# LED-Controller.net
KiCad netlist of a schematic drawn in EAGLE
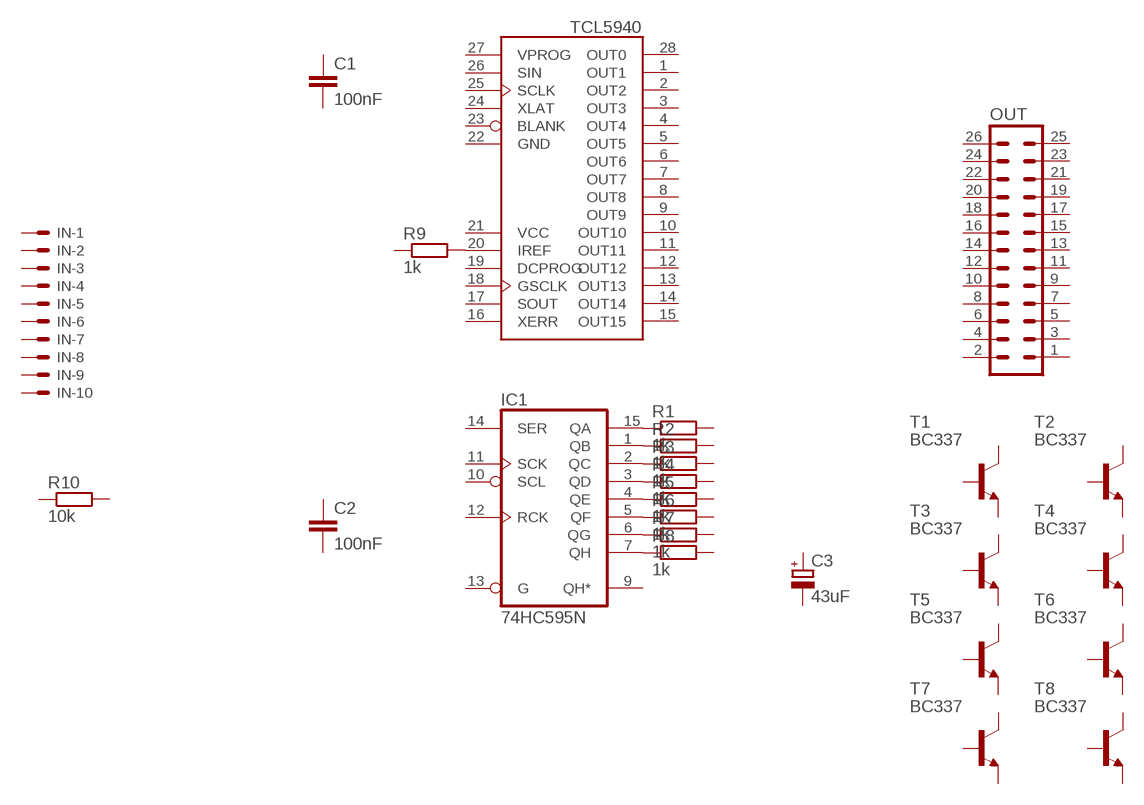
[diagram p0: schematic, sheet 1]

(export (version "E")
  (design (tool "Eeschema 10.0.6"))
  (components
    (comp (ref "C1")
      (value "100nF")
      (footprint "eagle-import:C025-024X044")
      (libsource (lib "eagle-import") (part "C-EU025-024X044"))
    )
    (comp (ref "C2")
      (value "100nF")
      (footprint "eagle-import:C025-024X044")
      (libsource (lib "eagle-import") (part "C-EU025-024X044"))
    )
    (comp (ref "C3")
      (value "43uF")
      (footprint "eagle-import:E2,5-6E")
      (libsource (lib "eagle-import") (part "CPOL-EUE2,5-6E"))
    )
    (comp (ref "IC1")
      (value "74HC595N")
      (footprint "eagle-import:DIL16")
      (libsource (lib "eagle-import") (part "74595NHC"))
    )
    (comp (ref "IC2")
      (value "TCL5940")
      (footprint "eagle-import:DIP28")
      (libsource (lib "eagle-import") (part "TCL5940"))
    )
    (comp (ref "IN")
      (value "KK-156-10")
      (footprint "eagle-import:KK-156-10")
      (libsource (lib "eagle-import") (part "KK-156-10"))
    )
    (comp (ref "OUT")
      (value "ML26")
      (footprint "eagle-import:ML26")
      (libsource (lib "eagle-import") (part "ML26"))
    )
    (comp (ref "R1")
      (value "1k")
      (footprint "eagle-import:0204_7")
      (libsource (lib "eagle-import") (part "R-EU_0204/7"))
    )
    (comp (ref "R2")
      (value "1k")
      (footprint "eagle-import:0204_7")
      (libsource (lib "eagle-import") (part "R-EU_0204/7"))
    )
    (comp (ref "R3")
      (value "1k")
      (footprint "eagle-import:0204_7")
      (libsource (lib "eagle-import") (part "R-EU_0204/7"))
    )
    (comp (ref "R4")
      (value "1k")
      (footprint "eagle-import:0204_7")
      (libsource (lib "eagle-import") (part "R-EU_0204/7"))
    )
    (comp (ref "R5")
      (value "1k")
      (footprint "eagle-import:0204_7")
      (libsource (lib "eagle-import") (part "R-EU_0204/7"))
    )
    (comp (ref "R6")
      (value "1k")
      (footprint "eagle-import:0204_7")
      (libsource (lib "eagle-import") (part "R-EU_0204/7"))
    )
    (comp (ref "R7")
      (value "1k")
      (footprint "eagle-import:0204_7")
      (libsource (lib "eagle-import") (part "R-EU_0204/7"))
    )
    (comp (ref "R8")
      (value "1k")
      (footprint "eagle-import:0204_7")
      (libsource (lib "eagle-import") (part "R-EU_0204/7"))
    )
    (comp (ref "R9")
      (value "1k")
      (footprint "eagle-import:0204_7")
      (libsource (lib "eagle-import") (part "R-EU_0204/7"))
    )
    (comp (ref "R10")
      (value "10k")
      (footprint "eagle-import:0204_7")
      (libsource (lib "eagle-import") (part "R-EU_0204/7"))
    )
    (comp (ref "T1")
      (value "BC337")
      (footprint "eagle-import:TO92")
      (libsource (lib "eagle-import") (part "BC337"))
    )
    (comp (ref "T2")
      (value "BC337")
      (footprint "eagle-import:TO92")
      (libsource (lib "eagle-import") (part "BC337"))
    )
    (comp (ref "T3")
      (value "BC337")
      (footprint "eagle-import:TO92")
      (libsource (lib "eagle-import") (part "BC337"))
    )
    (comp (ref "T4")
      (value "BC337")
      (footprint "eagle-import:TO92")
      (libsource (lib "eagle-import") (part "BC337"))
    )
    (comp (ref "T5")
      (value "BC337")
      (footprint "eagle-import:TO92")
      (libsource (lib "eagle-import") (part "BC337"))
    )
    (comp (ref "T6")
      (value "BC337")
      (footprint "eagle-import:TO92")
      (libsource (lib "eagle-import") (part "BC337"))
    )
    (comp (ref "T7")
      (value "BC337")
      (footprint "eagle-import:TO92")
      (libsource (lib "eagle-import") (part "BC337"))
    )
    (comp (ref "T8")
      (value "BC337")
      (footprint "eagle-import:TO92")
      (libsource (lib "eagle-import") (part "BC337"))
    )
  )
  (nets
    (net (code "1") (name "/GND") (class "Default")
      (node (ref "IC2") (pin "22") (pinfunction "GND_22") (pintype "power_in"))
    )
    (net (code "2") (name "/VCC") (class "Default")
      (node (ref "IC2") (pin "21") (pinfunction "VCC_21") (pintype "power_in"))
    )
    (net (code "3") (name "Net-(IC1A-QA)") (class "Default")
      (node (ref "IC1") (pin "15") (pinfunction "QA_15") (pintype "tri_state"))
      (node (ref "R1") (pin "1") (pinfunction "1_1") (pintype "passive"))
    )
    (net (code "4") (name "Net-(IC1A-QB)") (class "Default")
      (node (ref "IC1") (pin "1") (pinfunction "QB_1") (pintype "tri_state"))
      (node (ref "R2") (pin "1") (pinfunction "1_1") (pintype "passive"))
    )
    (net (code "5") (name "Net-(IC1A-QC)") (class "Default")
      (node (ref "IC1") (pin "2") (pinfunction "QC_2") (pintype "tri_state"))
      (node (ref "R3") (pin "1") (pinfunction "1_1") (pintype "passive"))
    )
    (net (code "6") (name "Net-(IC1A-QD)") (class "Default")
      (node (ref "IC1") (pin "3") (pinfunction "QD_3") (pintype "tri_state"))
      (node (ref "R4") (pin "1") (pinfunction "1_1") (pintype "passive"))
    )
    (net (code "7") (name "Net-(IC1A-QE)") (class "Default")
      (node (ref "IC1") (pin "4") (pinfunction "QE_4") (pintype "tri_state"))
      (node (ref "R5") (pin "1") (pinfunction "1_1") (pintype "passive"))
    )
    (net (code "8") (name "Net-(IC1A-QF)") (class "Default")
      (node (ref "IC1") (pin "5") (pinfunction "QF_5") (pintype "tri_state"))
      (node (ref "R6") (pin "1") (pinfunction "1_1") (pintype "passive"))
    )
    (net (code "9") (name "Net-(IC1A-QG)") (class "Default")
      (node (ref "IC1") (pin "6") (pinfunction "QG_6") (pintype "tri_state"))
      (node (ref "R7") (pin "1") (pinfunction "1_1") (pintype "passive"))
    )
    (net (code "10") (name "Net-(IC1A-QH)") (class "Default")
      (node (ref "IC1") (pin "7") (pinfunction "QH_7") (pintype "tri_state"))
      (node (ref "R8") (pin "1") (pinfunction "1_1") (pintype "passive"))
    )
    (net (code "11") (name "Net-(IC2-IREF)") (class "Default")
      (node (ref "IC2") (pin "20") (pinfunction "IREF_20") (pintype "input"))
      (node (ref "R9") (pin "2") (pinfunction "2_2") (pintype "passive"))
    )
    (net (code "12") (name "unconnected-(C1-Pad1)") (class "Default")
      (node (ref "C1") (pin "1") (pinfunction "1_1") (pintype "passive"))
    )
    (net (code "13") (name "unconnected-(C1-Pad2)") (class "Default")
      (node (ref "C1") (pin "2") (pinfunction "2_2") (pintype "passive"))
    )
    (net (code "14") (name "unconnected-(C2-Pad1)") (class "Default")
      (node (ref "C2") (pin "1") (pinfunction "1_1") (pintype "passive"))
    )
    (net (code "15") (name "unconnected-(C2-Pad2)") (class "Default")
      (node (ref "C2") (pin "2") (pinfunction "2_2") (pintype "passive"))
    )
    (net (code "16") (name "unconnected-(C3-Pad+)") (class "Default")
      (node (ref "C3") (pin "+") (pinfunction "+_+") (pintype "passive"))
    )
    (net (code "17") (name "unconnected-(C3-Pad-)") (class "Default")
      (node (ref "C3") (pin "-") (pinfunction "-_-") (pintype "passive"))
    )
    (net (code "18") (name "unconnected-(IC1A-G-Pad13)") (class "Default")
      (node (ref "IC1") (pin "13") (pinfunction "G_13") (pintype "input"))
    )
    (net (code "19") (name "unconnected-(IC1A-QH*-Pad9)") (class "Default")
      (node (ref "IC1") (pin "9") (pinfunction "QH*_9") (pintype "tri_state"))
    )
    (net (code "20") (name "unconnected-(IC1A-RCK-Pad12)") (class "Default")
      (node (ref "IC1") (pin "12") (pinfunction "RCK_12") (pintype "input"))
    )
    (net (code "21") (name "unconnected-(IC1A-SCK-Pad11)") (class "Default")
      (node (ref "IC1") (pin "11") (pinfunction "SCK_11") (pintype "input"))
    )
    (net (code "22") (name "unconnected-(IC1A-SCL-Pad10)") (class "Default")
      (node (ref "IC1") (pin "10") (pinfunction "SCL_10") (pintype "input"))
    )
    (net (code "23") (name "unconnected-(IC1A-SER-Pad14)") (class "Default")
      (node (ref "IC1") (pin "14") (pinfunction "SER_14") (pintype "input"))
    )
    (net (code "24") (name "unconnected-(IC2-BLANK-Pad23)") (class "Default")
      (node (ref "IC2") (pin "23") (pinfunction "BLANK_23") (pintype "input"))
    )
    (net (code "25") (name "unconnected-(IC2-DCPROG-Pad19)") (class "Default")
      (node (ref "IC2") (pin "19") (pinfunction "DCPROG_19") (pintype "input"))
    )
    (net (code "26") (name "unconnected-(IC2-GSCLK-Pad18)") (class "Default")
      (node (ref "IC2") (pin "18") (pinfunction "GSCLK_18") (pintype "input"))
    )
    (net (code "27") (name "unconnected-(IC2-OUT0-Pad28)") (class "Default")
      (node (ref "IC2") (pin "28") (pinfunction "OUT0_28") (pintype "output"))
    )
    (net (code "28") (name "unconnected-(IC2-OUT1-Pad1)") (class "Default")
      (node (ref "IC2") (pin "1") (pinfunction "OUT1_1") (pintype "output"))
    )
    (net (code "29") (name "unconnected-(IC2-OUT2-Pad2)") (class "Default")
      (node (ref "IC2") (pin "2") (pinfunction "OUT2_2") (pintype "output"))
    )
    (net (code "30") (name "unconnected-(IC2-OUT3-Pad3)") (class "Default")
      (node (ref "IC2") (pin "3") (pinfunction "OUT3_3") (pintype "output"))
    )
    (net (code "31") (name "unconnected-(IC2-OUT4-Pad4)") (class "Default")
      (node (ref "IC2") (pin "4") (pinfunction "OUT4_4") (pintype "output"))
    )
    (net (code "32") (name "unconnected-(IC2-OUT5-Pad5)") (class "Default")
      (node (ref "IC2") (pin "5") (pinfunction "OUT5_5") (pintype "output"))
    )
    (net (code "33") (name "unconnected-(IC2-OUT6-Pad6)") (class "Default")
      (node (ref "IC2") (pin "6") (pinfunction "OUT6_6") (pintype "output"))
    )
    (net (code "34") (name "unconnected-(IC2-OUT7-Pad7)") (class "Default")
      (node (ref "IC2") (pin "7") (pinfunction "OUT7_7") (pintype "output"))
    )
    (net (code "35") (name "unconnected-(IC2-OUT8-Pad8)") (class "Default")
      (node (ref "IC2") (pin "8") (pinfunction "OUT8_8") (pintype "output"))
    )
    (net (code "36") (name "unconnected-(IC2-OUT9-Pad9)") (class "Default")
      (node (ref "IC2") (pin "9") (pinfunction "OUT9_9") (pintype "output"))
    )
    (net (code "37") (name "unconnected-(IC2-OUT10-Pad10)") (class "Default")
      (node (ref "IC2") (pin "10") (pinfunction "OUT10_10") (pintype "output"))
    )
    (net (code "38") (name "unconnected-(IC2-OUT11-Pad11)") (class "Default")
      (node (ref "IC2") (pin "11") (pinfunction "OUT11_11") (pintype "output"))
    )
    (net (code "39") (name "unconnected-(IC2-OUT12-Pad12)") (class "Default")
      (node (ref "IC2") (pin "12") (pinfunction "OUT12_12") (pintype "output"))
    )
    (net (code "40") (name "unconnected-(IC2-OUT13-Pad13)") (class "Default")
      (node (ref "IC2") (pin "13") (pinfunction "OUT13_13") (pintype "output"))
    )
    (net (code "41") (name "unconnected-(IC2-OUT14-Pad14)") (class "Default")
      (node (ref "IC2") (pin "14") (pinfunction "OUT14_14") (pintype "output"))
    )
    (net (code "42") (name "unconnected-(IC2-OUT15-Pad15)") (class "Default")
      (node (ref "IC2") (pin "15") (pinfunction "OUT15_15") (pintype "output"))
    )
    (net (code "43") (name "unconnected-(IC2-SCLK-Pad25)") (class "Default")
      (node (ref "IC2") (pin "25") (pinfunction "SCLK_25") (pintype "input"))
    )
    (net (code "44") (name "unconnected-(IC2-SIN-Pad26)") (class "Default")
      (node (ref "IC2") (pin "26") (pinfunction "SIN_26") (pintype "input"))
    )
    (net (code "45") (name "unconnected-(IC2-SOUT-Pad17)") (class "Default")
      (node (ref "IC2") (pin "17") (pinfunction "SOUT_17") (pintype "output"))
    )
    (net (code "46") (name "unconnected-(IC2-VPROG-Pad27)") (class "Default")
      (node (ref "IC2") (pin "27") (pinfunction "VPROG_27") (pintype "bidirectional"))
    )
    (net (code "47") (name "unconnected-(IC2-XERR-Pad16)") (class "Default")
      (node (ref "IC2") (pin "16") (pinfunction "XERR_16") (pintype "output"))
    )
    (net (code "48") (name "unconnected-(IC2-XLAT-Pad24)") (class "Default")
      (node (ref "IC2") (pin "24") (pinfunction "XLAT_24") (pintype "input"))
    )
    (net (code "49") (name "unconnected-(INA-S-Pad1)") (class "Default")
      (node (ref "IN") (pin "1") (pinfunction "S_1") (pintype "passive"))
    )
    (net (code "50") (name "unconnected-(INB-S-Pad10)") (class "Default")
      (node (ref "IN") (pin "10") (pinfunction "S_10") (pintype "passive"))
    )
    (net (code "51") (name "unconnected-(INC-S-Pad2)") (class "Default")
      (node (ref "IN") (pin "2") (pinfunction "S_2") (pintype "passive"))
    )
    (net (code "52") (name "unconnected-(IND-S-Pad3)") (class "Default")
      (node (ref "IN") (pin "3") (pinfunction "S_3") (pintype "passive"))
    )
    (net (code "53") (name "unconnected-(INE-S-Pad4)") (class "Default")
      (node (ref "IN") (pin "4") (pinfunction "S_4") (pintype "passive"))
    )
    (net (code "54") (name "unconnected-(INF-S-Pad5)") (class "Default")
      (node (ref "IN") (pin "5") (pinfunction "S_5") (pintype "passive"))
    )
    (net (code "55") (name "unconnected-(ING-S-Pad6)") (class "Default")
      (node (ref "IN") (pin "6") (pinfunction "S_6") (pintype "passive"))
    )
    (net (code "56") (name "unconnected-(INH-S-Pad7)") (class "Default")
      (node (ref "IN") (pin "7") (pinfunction "S_7") (pintype "passive"))
    )
    (net (code "57") (name "unconnected-(INI-S-Pad8)") (class "Default")
      (node (ref "IN") (pin "8") (pinfunction "S_8") (pintype "passive"))
    )
    (net (code "58") (name "unconnected-(INJ-S-Pad9)") (class "Default")
      (node (ref "IN") (pin "9") (pinfunction "S_9") (pintype "passive"))
    )
    (net (code "59") (name "unconnected-(OUT-Pad1)") (class "Default")
      (node (ref "OUT") (pin "1") (pinfunction "1_1") (pintype "passive"))
    )
    (net (code "60") (name "unconnected-(OUT-Pad2)") (class "Default")
      (node (ref "OUT") (pin "2") (pinfunction "2_2") (pintype "passive"))
    )
    (net (code "61") (name "unconnected-(OUT-Pad3)") (class "Default")
      (node (ref "OUT") (pin "3") (pinfunction "3_3") (pintype "passive"))
    )
    (net (code "62") (name "unconnected-(OUT-Pad4)") (class "Default")
      (node (ref "OUT") (pin "4") (pinfunction "4_4") (pintype "passive"))
    )
    (net (code "63") (name "unconnected-(OUT-Pad5)") (class "Default")
      (node (ref "OUT") (pin "5") (pinfunction "5_5") (pintype "passive"))
    )
    (net (code "64") (name "unconnected-(OUT-Pad6)") (class "Default")
      (node (ref "OUT") (pin "6") (pinfunction "6_6") (pintype "passive"))
    )
    (net (code "65") (name "unconnected-(OUT-Pad7)") (class "Default")
      (node (ref "OUT") (pin "7") (pinfunction "7_7") (pintype "passive"))
    )
    (net (code "66") (name "unconnected-(OUT-Pad8)") (class "Default")
      (node (ref "OUT") (pin "8") (pinfunction "8_8") (pintype "passive"))
    )
    (net (code "67") (name "unconnected-(OUT-Pad9)") (class "Default")
      (node (ref "OUT") (pin "9") (pinfunction "9_9") (pintype "passive"))
    )
    (net (code "68") (name "unconnected-(OUT-Pad10)") (class "Default")
      (node (ref "OUT") (pin "10") (pinfunction "10_10") (pintype "passive"))
    )
    (net (code "69") (name "unconnected-(OUT-Pad11)") (class "Default")
      (node (ref "OUT") (pin "11") (pinfunction "11_11") (pintype "passive"))
    )
    (net (code "70") (name "unconnected-(OUT-Pad12)") (class "Default")
      (node (ref "OUT") (pin "12") (pinfunction "12_12") (pintype "passive"))
    )
    (net (code "71") (name "unconnected-(OUT-Pad13)") (class "Default")
      (node (ref "OUT") (pin "13") (pinfunction "13_13") (pintype "passive"))
    )
    (net (code "72") (name "unconnected-(OUT-Pad14)") (class "Default")
      (node (ref "OUT") (pin "14") (pinfunction "14_14") (pintype "passive"))
    )
    (net (code "73") (name "unconnected-(OUT-Pad15)") (class "Default")
      (node (ref "OUT") (pin "15") (pinfunction "15_15") (pintype "passive"))
    )
    (net (code "74") (name "unconnected-(OUT-Pad16)") (class "Default")
      (node (ref "OUT") (pin "16") (pinfunction "16_16") (pintype "passive"))
    )
    (net (code "75") (name "unconnected-(OUT-Pad17)") (class "Default")
      (node (ref "OUT") (pin "17") (pinfunction "17_17") (pintype "passive"))
    )
    (net (code "76") (name "unconnected-(OUT-Pad18)") (class "Default")
      (node (ref "OUT") (pin "18") (pinfunction "18_18") (pintype "passive"))
    )
    (net (code "77") (name "unconnected-(OUT-Pad19)") (class "Default")
      (node (ref "OUT") (pin "19") (pinfunction "19_19") (pintype "passive"))
    )
    (net (code "78") (name "unconnected-(OUT-Pad20)") (class "Default")
      (node (ref "OUT") (pin "20") (pinfunction "20_20") (pintype "passive"))
    )
    (net (code "79") (name "unconnected-(OUT-Pad21)") (class "Default")
      (node (ref "OUT") (pin "21") (pinfunction "21_21") (pintype "passive"))
    )
    (net (code "80") (name "unconnected-(OUT-Pad22)") (class "Default")
      (node (ref "OUT") (pin "22") (pinfunction "22_22") (pintype "passive"))
    )
    (net (code "81") (name "unconnected-(OUT-Pad23)") (class "Default")
      (node (ref "OUT") (pin "23") (pinfunction "23_23") (pintype "passive"))
    )
    (net (code "82") (name "unconnected-(OUT-Pad24)") (class "Default")
      (node (ref "OUT") (pin "24") (pinfunction "24_24") (pintype "passive"))
    )
    (net (code "83") (name "unconnected-(OUT-Pad25)") (class "Default")
      (node (ref "OUT") (pin "25") (pinfunction "25_25") (pintype "passive"))
    )
    (net (code "84") (name "unconnected-(OUT-Pad26)") (class "Default")
      (node (ref "OUT") (pin "26") (pinfunction "26_26") (pintype "passive"))
    )
    (net (code "85") (name "unconnected-(R1-Pad2)") (class "Default")
      (node (ref "R1") (pin "2") (pinfunction "2_2") (pintype "passive"))
    )
    (net (code "86") (name "unconnected-(R2-Pad2)") (class "Default")
      (node (ref "R2") (pin "2") (pinfunction "2_2") (pintype "passive"))
    )
    (net (code "87") (name "unconnected-(R3-Pad2)") (class "Default")
      (node (ref "R3") (pin "2") (pinfunction "2_2") (pintype "passive"))
    )
    (net (code "88") (name "unconnected-(R4-Pad2)") (class "Default")
      (node (ref "R4") (pin "2") (pinfunction "2_2") (pintype "passive"))
    )
    (net (code "89") (name "unconnected-(R5-Pad2)") (class "Default")
      (node (ref "R5") (pin "2") (pinfunction "2_2") (pintype "passive"))
    )
    (net (code "90") (name "unconnected-(R6-Pad2)") (class "Default")
      (node (ref "R6") (pin "2") (pinfunction "2_2") (pintype "passive"))
    )
    (net (code "91") (name "unconnected-(R7-Pad2)") (class "Default")
      (node (ref "R7") (pin "2") (pinfunction "2_2") (pintype "passive"))
    )
    (net (code "92") (name "unconnected-(R8-Pad2)") (class "Default")
      (node (ref "R8") (pin "2") (pinfunction "2_2") (pintype "passive"))
    )
    (net (code "93") (name "unconnected-(R9-Pad1)") (class "Default")
      (node (ref "R9") (pin "1") (pinfunction "1_1") (pintype "passive"))
    )
    (net (code "94") (name "unconnected-(R10-Pad1)") (class "Default")
      (node (ref "R10") (pin "1") (pinfunction "1_1") (pintype "passive"))
    )
    (net (code "95") (name "unconnected-(R10-Pad2)") (class "Default")
      (node (ref "R10") (pin "2") (pinfunction "2_2") (pintype "passive"))
    )
    (net (code "96") (name "unconnected-(T1-B-Pad2)") (class "Default")
      (node (ref "T1") (pin "2") (pinfunction "B_2") (pintype "passive"))
    )
    (net (code "97") (name "unconnected-(T1-C-Pad3)") (class "Default")
      (node (ref "T1") (pin "3") (pinfunction "C_3") (pintype "passive"))
    )
    (net (code "98") (name "unconnected-(T1-E-Pad1)") (class "Default")
      (node (ref "T1") (pin "1") (pinfunction "E_1") (pintype "passive"))
    )
    (net (code "99") (name "unconnected-(T2-B-Pad2)") (class "Default")
      (node (ref "T2") (pin "2") (pinfunction "B_2") (pintype "passive"))
    )
    (net (code "100") (name "unconnected-(T2-C-Pad3)") (class "Default")
      (node (ref "T2") (pin "3") (pinfunction "C_3") (pintype "passive"))
    )
    (net (code "101") (name "unconnected-(T2-E-Pad1)") (class "Default")
      (node (ref "T2") (pin "1") (pinfunction "E_1") (pintype "passive"))
    )
    (net (code "102") (name "unconnected-(T3-B-Pad2)") (class "Default")
      (node (ref "T3") (pin "2") (pinfunction "B_2") (pintype "passive"))
    )
    (net (code "103") (name "unconnected-(T3-C-Pad3)") (class "Default")
      (node (ref "T3") (pin "3") (pinfunction "C_3") (pintype "passive"))
    )
    (net (code "104") (name "unconnected-(T3-E-Pad1)") (class "Default")
      (node (ref "T3") (pin "1") (pinfunction "E_1") (pintype "passive"))
    )
    (net (code "105") (name "unconnected-(T4-B-Pad2)") (class "Default")
      (node (ref "T4") (pin "2") (pinfunction "B_2") (pintype "passive"))
    )
    (net (code "106") (name "unconnected-(T4-C-Pad3)") (class "Default")
      (node (ref "T4") (pin "3") (pinfunction "C_3") (pintype "passive"))
    )
    (net (code "107") (name "unconnected-(T4-E-Pad1)") (class "Default")
      (node (ref "T4") (pin "1") (pinfunction "E_1") (pintype "passive"))
    )
    (net (code "108") (name "unconnected-(T5-B-Pad2)") (class "Default")
      (node (ref "T5") (pin "2") (pinfunction "B_2") (pintype "passive"))
    )
    (net (code "109") (name "unconnected-(T5-C-Pad3)") (class "Default")
      (node (ref "T5") (pin "3") (pinfunction "C_3") (pintype "passive"))
    )
    (net (code "110") (name "unconnected-(T5-E-Pad1)") (class "Default")
      (node (ref "T5") (pin "1") (pinfunction "E_1") (pintype "passive"))
    )
    (net (code "111") (name "unconnected-(T6-B-Pad2)") (class "Default")
      (node (ref "T6") (pin "2") (pinfunction "B_2") (pintype "passive"))
    )
    (net (code "112") (name "unconnected-(T6-C-Pad3)") (class "Default")
      (node (ref "T6") (pin "3") (pinfunction "C_3") (pintype "passive"))
    )
    (net (code "113") (name "unconnected-(T6-E-Pad1)") (class "Default")
      (node (ref "T6") (pin "1") (pinfunction "E_1") (pintype "passive"))
    )
    (net (code "114") (name "unconnected-(T7-B-Pad2)") (class "Default")
      (node (ref "T7") (pin "2") (pinfunction "B_2") (pintype "passive"))
    )
    (net (code "115") (name "unconnected-(T7-C-Pad3)") (class "Default")
      (node (ref "T7") (pin "3") (pinfunction "C_3") (pintype "passive"))
    )
    (net (code "116") (name "unconnected-(T7-E-Pad1)") (class "Default")
      (node (ref "T7") (pin "1") (pinfunction "E_1") (pintype "passive"))
    )
    (net (code "117") (name "unconnected-(T8-B-Pad2)") (class "Default")
      (node (ref "T8") (pin "2") (pinfunction "B_2") (pintype "passive"))
    )
    (net (code "118") (name "unconnected-(T8-C-Pad3)") (class "Default")
      (node (ref "T8") (pin "3") (pinfunction "C_3") (pintype "passive"))
    )
    (net (code "119") (name "unconnected-(T8-E-Pad1)") (class "Default")
      (node (ref "T8") (pin "1") (pinfunction "E_1") (pintype "passive"))
    )
  )
)
